# MCU.net
KiCad netlist of a schematic drawn in Altium Designer
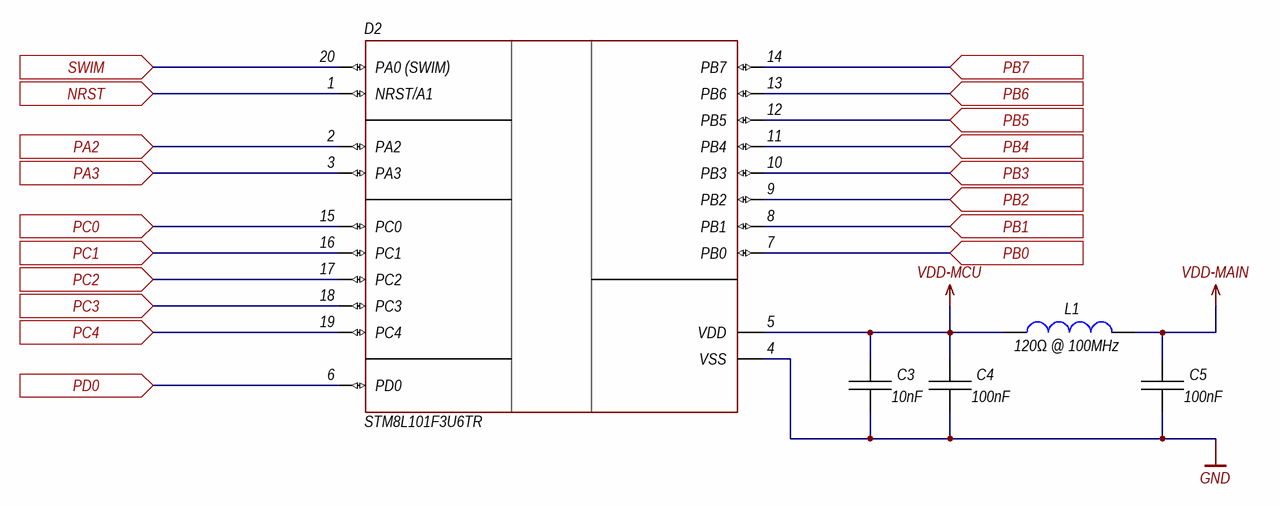
[diagram p0: MCU.SchDoc]

(export (version "E")
  (design (tool "Eeschema 10.0.6"))
  (components
    (comp (ref "C3") (value "10nF") (footprint "CH0402C") (libsource (lib "Discrete") (part "Capacitor")))
    (comp (ref "C4") (value "100nF") (footprint "CH0402C") (libsource (lib "Discrete") (part "Capacitor")))
    (comp (ref "C5") (value "100nF") (footprint "CH0402C") (libsource (lib "Discrete") (part "Capacitor")))
    (comp (ref "D2")
      (value "STM8L101F3U6TR")
      (footprint "20-UFQFPN")
      (description "STM8")
      (fields (field (name "MANUFACTURER") "ST Microelectronics"))
      (libsource (lib "Digital") (part "STM8L101F3U6"))
    )
    (comp (ref "L1")
      (value "120Ω @ 100MHz")
      (footprint "CH0402L")
      (libsource (lib "Discrete") (part "Inductor"))
    )
  )
  (nets
    (net (code "1") (name "/NRST") (class "Default")
      (node (ref "D2") (pin "1") (pinfunction "NRST/A1_1") (pintype "bidirectional"))
    )
    (net (code "2") (name "/PA2") (class "Default")
      (node (ref "D2") (pin "2") (pinfunction "PA2_2") (pintype "bidirectional"))
    )
    (net (code "3") (name "/PA3") (class "Default")
      (node (ref "D2") (pin "3") (pinfunction "PA3_3") (pintype "bidirectional"))
    )
    (net (code "4") (name "/PB0") (class "Default")
      (node (ref "D2") (pin "7") (pinfunction "PB0_7") (pintype "bidirectional"))
    )
    (net (code "5") (name "/PB1") (class "Default")
      (node (ref "D2") (pin "8") (pinfunction "PB1_8") (pintype "bidirectional"))
    )
    (net (code "6") (name "/PB2") (class "Default")
      (node (ref "D2") (pin "9") (pinfunction "PB2_9") (pintype "bidirectional"))
    )
    (net (code "7") (name "/PB3") (class "Default")
      (node (ref "D2") (pin "10") (pinfunction "PB3_10") (pintype "bidirectional"))
    )
    (net (code "8") (name "/PB4") (class "Default")
      (node (ref "D2") (pin "11") (pinfunction "PB4_11") (pintype "bidirectional"))
    )
    (net (code "9") (name "/PB5") (class "Default")
      (node (ref "D2") (pin "12") (pinfunction "PB5_12") (pintype "bidirectional"))
    )
    (net (code "10") (name "/PB6") (class "Default")
      (node (ref "D2") (pin "13") (pinfunction "PB6_13") (pintype "bidirectional"))
    )
    (net (code "11") (name "/PB7") (class "Default")
      (node (ref "D2") (pin "14") (pinfunction "PB7_14") (pintype "bidirectional"))
    )
    (net (code "12") (name "/PC0") (class "Default")
      (node (ref "D2") (pin "15") (pinfunction "PC0_15") (pintype "bidirectional"))
    )
    (net (code "13") (name "/PC1") (class "Default")
      (node (ref "D2") (pin "16") (pinfunction "PC1_16") (pintype "bidirectional"))
    )
    (net (code "14") (name "/PC2") (class "Default")
      (node (ref "D2") (pin "17") (pinfunction "PC2_17") (pintype "bidirectional"))
    )
    (net (code "15") (name "/PC3") (class "Default")
      (node (ref "D2") (pin "18") (pinfunction "PC3_18") (pintype "bidirectional"))
    )
    (net (code "16") (name "/PC4") (class "Default")
      (node (ref "D2") (pin "19") (pinfunction "PC4_19") (pintype "bidirectional"))
    )
    (net (code "17") (name "/PD0") (class "Default")
      (node (ref "D2") (pin "6") (pinfunction "PD0_6") (pintype "bidirectional"))
    )
    (net (code "18") (name "/SWIM") (class "Default")
      (node (ref "D2") (pin "20") (pinfunction "PA0_(SWIM)_20") (pintype "bidirectional"))
    )
    (net (code "19") (name "GND") (class "Default")
      (node (ref "C3") (pin "1") (pinfunction "1_1") (pintype "passive"))
      (node (ref "C4") (pin "1") (pinfunction "1_1") (pintype "passive"))
      (node (ref "C5") (pin "1") (pinfunction "1_1") (pintype "passive"))
      (node (ref "D2") (pin "4") (pinfunction "VSS_4") (pintype "power_in"))
    )
    (net (code "20") (name "VDD-MAIN") (class "Default")
      (node (ref "C5") (pin "2") (pinfunction "2_2") (pintype "passive"))
      (node (ref "L1") (pin "1") (pinfunction "1_1") (pintype "passive"))
    )
    (net (code "21") (name "VDD-MCU") (class "Default")
      (node (ref "C3") (pin "2") (pinfunction "2_2") (pintype "passive"))
      (node (ref "C4") (pin "2") (pinfunction "2_2") (pintype "passive"))
      (node (ref "D2") (pin "5") (pinfunction "VDD_5") (pintype "power_in"))
      (node (ref "L1") (pin "2") (pinfunction "2_2") (pintype "passive"))
    )
  )
)
